# VALVEBOARD_ValvePower.net
KiCad netlist of a schematic drawn in Altium Designer
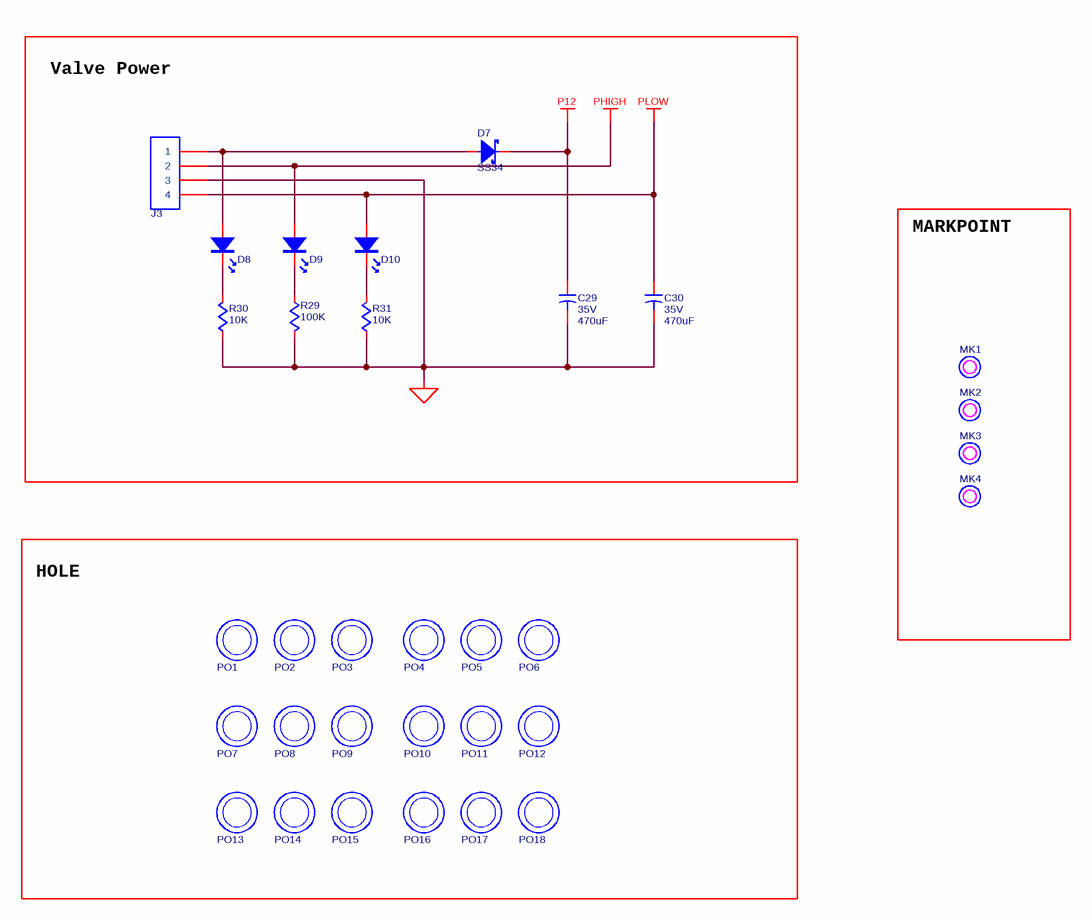
[diagram p0: VALVEBOARD_ValvePower.SchDoc]

(export (version "E")
  (design (tool "Eeschema 10.0.6"))
  (components
    (comp (ref "C29")
      (value "470uF")
      (footprint "C_10_10R2")
      (fields (field (name "VOLTAGE") "35V") (field (name "Comment") "C-POL"))
      (libsource (lib "zynq") (part "C-POL"))
    )
    (comp (ref "C30")
      (value "470uF")
      (footprint "C_10_10R2")
      (fields (field (name "VOLTAGE") "35V") (field (name "Comment") "C-POL"))
      (libsource (lib "zynq") (part "C-POL"))
    )
    (comp (ref "D7") (value "SS34") (footprint "SS34") (libsource (lib "zynq") (part "SS34")))
    (comp (ref "D8") (value "LED") (footprint "zynq:LED0603") (libsource (lib "zynq") (part "LED")))
    (comp (ref "D9") (value "LED") (footprint "zynq:LED0603") (libsource (lib "zynq") (part "LED")))
    (comp (ref "D10") (value "LED") (footprint "zynq:LED0603") (libsource (lib "zynq") (part "LED")))
    (comp (ref "J3")
      (value "HDR1X4")
      (footprint "zynq:KF301-5.0-4P")
      (libsource (lib "zynq") (part "HDR1X4"))
    )
    (comp (ref "MK1")
      (value "MARKPOINT")
      (footprint "zynq:MARKPOINT-1.0")
      (libsource (lib "zynq") (part "MARKPOINT"))
    )
    (comp (ref "MK2")
      (value "MARKPOINT")
      (footprint "zynq:MARKPOINT-1.0")
      (libsource (lib "zynq") (part "MARKPOINT"))
    )
    (comp (ref "MK3")
      (value "MARKPOINT")
      (footprint "zynq:MARKPOINT-1.0")
      (libsource (lib "zynq") (part "MARKPOINT"))
    )
    (comp (ref "MK4")
      (value "MARKPOINT")
      (footprint "zynq:MARKPOINT-1.0")
      (libsource (lib "zynq") (part "MARKPOINT"))
    )
    (comp (ref "PO1")
      (value "POSHOLE")
      (footprint "zynq:POSHOLE-3.2")
      (libsource (lib "zynq") (part "POSHOLE"))
    )
    (comp (ref "PO2")
      (value "POSHOLE")
      (footprint "zynq:POSHOLE-3.2")
      (libsource (lib "zynq") (part "POSHOLE"))
    )
    (comp (ref "PO3")
      (value "POSHOLE")
      (footprint "zynq:POSHOLE-3.2")
      (libsource (lib "zynq") (part "POSHOLE"))
    )
    (comp (ref "PO4")
      (value "POSHOLE")
      (footprint "zynq:POSHOLE-3.2")
      (libsource (lib "zynq") (part "POSHOLE"))
    )
    (comp (ref "PO5")
      (value "POSHOLE")
      (footprint "zynq:POSHOLE-3.2")
      (libsource (lib "zynq") (part "POSHOLE"))
    )
    (comp (ref "PO6")
      (value "POSHOLE")
      (footprint "zynq:POSHOLE-3.2")
      (libsource (lib "zynq") (part "POSHOLE"))
    )
    (comp (ref "PO7")
      (value "POSHOLE")
      (footprint "zynq:POSHOLE-3.2")
      (libsource (lib "zynq") (part "POSHOLE"))
    )
    (comp (ref "PO8")
      (value "POSHOLE")
      (footprint "zynq:POSHOLE-3.2")
      (libsource (lib "zynq") (part "POSHOLE"))
    )
    (comp (ref "PO9")
      (value "POSHOLE")
      (footprint "zynq:POSHOLE-3.2")
      (libsource (lib "zynq") (part "POSHOLE"))
    )
    (comp (ref "PO10")
      (value "POSHOLE")
      (footprint "zynq:POSHOLE-3.2")
      (libsource (lib "zynq") (part "POSHOLE"))
    )
    (comp (ref "PO11")
      (value "POSHOLE")
      (footprint "zynq:POSHOLE-3.2")
      (libsource (lib "zynq") (part "POSHOLE"))
    )
    (comp (ref "PO12")
      (value "POSHOLE")
      (footprint "zynq:POSHOLE-3.2")
      (libsource (lib "zynq") (part "POSHOLE"))
    )
    (comp (ref "PO13")
      (value "POSHOLE")
      (footprint "zynq:POSHOLE-3.2")
      (libsource (lib "zynq") (part "POSHOLE"))
    )
    (comp (ref "PO14")
      (value "POSHOLE")
      (footprint "zynq:POSHOLE-3.2")
      (libsource (lib "zynq") (part "POSHOLE"))
    )
    (comp (ref "PO15")
      (value "POSHOLE")
      (footprint "zynq:POSHOLE-3.2")
      (libsource (lib "zynq") (part "POSHOLE"))
    )
    (comp (ref "PO16")
      (value "POSHOLE")
      (footprint "zynq:POSHOLE-3.2")
      (libsource (lib "zynq") (part "POSHOLE"))
    )
    (comp (ref "PO17")
      (value "POSHOLE")
      (footprint "zynq:POSHOLE-3.2")
      (libsource (lib "zynq") (part "POSHOLE"))
    )
    (comp (ref "PO18")
      (value "POSHOLE")
      (footprint "zynq:POSHOLE-3.2")
      (libsource (lib "zynq") (part "POSHOLE"))
    )
    (comp (ref "R29")
      (value "100K")
      (footprint "R1206")
      (fields (field (name "Comment") "R"))
      (libsource (lib "zynq") (part "R"))
    )
    (comp (ref "R30")
      (value "10K")
      (footprint "zynq:R0805")
      (fields (field (name "Comment") "R"))
      (libsource (lib "zynq") (part "R"))
    )
    (comp (ref "R31")
      (value "10K")
      (footprint "zynq:R0805")
      (fields (field (name "Comment") "R"))
      (libsource (lib "zynq") (part "R"))
    )
  )
  (nets
    (net (code "2") (name "Net-(D7-Pad2)") (class "Default")
      (node (ref "D7") (pin "2") (pinfunction "2_2") (pintype "passive"))
      (node (ref "D8") (pin "2") (pinfunction "2_2") (pintype "passive"))
      (node (ref "J3") (pin "1") (pinfunction "1_1") (pintype "passive"))
    )
    (net (code "3") (name "Net-(D8-Pad1)") (class "Default")
      (node (ref "D8") (pin "1") (pinfunction "1_1") (pintype "passive"))
      (node (ref "R30") (pin "1") (pinfunction "1_1") (pintype "passive"))
    )
    (net (code "4") (name "Net-(D9-Pad1)") (class "Default")
      (node (ref "D9") (pin "1") (pinfunction "1_1") (pintype "passive"))
      (node (ref "R29") (pin "2") (pinfunction "2_2") (pintype "passive"))
    )
    (net (code "5") (name "Net-(D10-Pad1)") (class "Default")
      (node (ref "D10") (pin "1") (pinfunction "1_1") (pintype "passive"))
      (node (ref "R31") (pin "1") (pinfunction "1_1") (pintype "passive"))
    )
    (net (code "6") (name "P12") (class "Default")
      (node (ref "C29") (pin "1") (pinfunction "S_1") (pintype "passive"))
      (node (ref "D7") (pin "1") (pinfunction "1_1") (pintype "passive"))
    )
    (net (code "7") (name "PGND") (class "Default")
      (node (ref "C29") (pin "2") (pinfunction "2_2") (pintype "passive"))
      (node (ref "C30") (pin "2") (pinfunction "2_2") (pintype "passive"))
      (node (ref "J3") (pin "3") (pinfunction "3_3") (pintype "passive"))
      (node (ref "R29") (pin "1") (pinfunction "1_1") (pintype "passive"))
      (node (ref "R30") (pin "2") (pinfunction "2_2") (pintype "passive"))
      (node (ref "R31") (pin "2") (pinfunction "2_2") (pintype "passive"))
    )
    (net (code "8") (name "PHIGH") (class "Default")
      (node (ref "D9") (pin "2") (pinfunction "2_2") (pintype "passive"))
      (node (ref "J3") (pin "2") (pinfunction "2_2") (pintype "passive"))
    )
    (net (code "9") (name "PLOW") (class "Default")
      (node (ref "C30") (pin "1") (pinfunction "S_1") (pintype "passive"))
      (node (ref "D10") (pin "2") (pinfunction "2_2") (pintype "passive"))
      (node (ref "J3") (pin "4") (pinfunction "4_4") (pintype "passive"))
    )
  )
)
